# Driver.net
KiCad netlist of a schematic drawn in Altium Designer
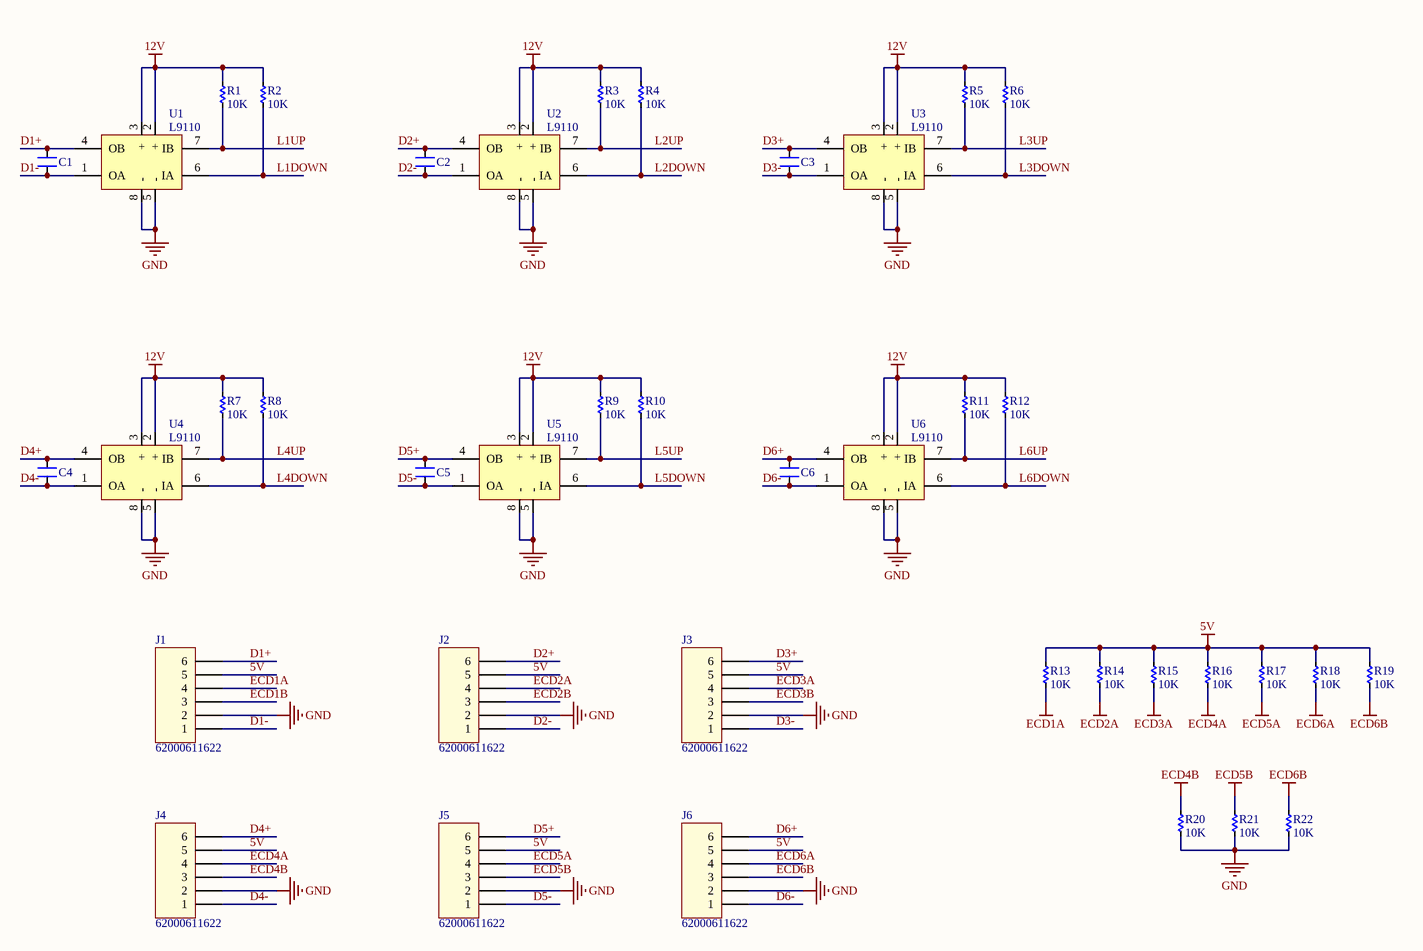
[diagram p0: Driver.SchDoc]

(export (version "E")
  (design (tool "Eeschema 10.0.6"))
  (components
    (comp (ref "C1") (value "XXpF") (footprint "CN2-LT") (libsource (lib "LIBRARY") (part "CN")))
    (comp (ref "C2") (value "XXpF") (footprint "CN2-LT") (libsource (lib "LIBRARY") (part "CN")))
    (comp (ref "C3") (value "XXpF") (footprint "CN2-LT") (libsource (lib "LIBRARY") (part "CN")))
    (comp (ref "C4") (value "XXpF") (footprint "CN2-LT") (libsource (lib "LIBRARY") (part "CN")))
    (comp (ref "C5") (value "XXpF") (footprint "CN2-LT") (libsource (lib "LIBRARY") (part "CN")))
    (comp (ref "C6") (value "XXpF") (footprint "CN2-LT") (libsource (lib "LIBRARY") (part "CN")))
    (comp (ref "J1")
      (value "62000611622")
      (footprint "62000611622")
      (description "WR-WTB 2.00mm Male Vertical Shrouded Header, 6p")
      (fields (field (name "PUBLISHER") "Wurth Elektronik"))
      (libsource (lib "Header2.0") (part "62000611622"))
    )
    (comp (ref "J2")
      (value "62000611622")
      (footprint "62000611622")
      (description "WR-WTB 2.00mm Male Vertical Shrouded Header, 6p")
      (fields (field (name "PUBLISHER") "Wurth Elektronik"))
      (libsource (lib "Header2.0") (part "62000611622"))
    )
    (comp (ref "J3")
      (value "62000611622")
      (footprint "62000611622")
      (description "WR-WTB 2.00mm Male Vertical Shrouded Header, 6p")
      (fields (field (name "PUBLISHER") "Wurth Elektronik"))
      (libsource (lib "Header2.0") (part "62000611622"))
    )
    (comp (ref "J4")
      (value "62000611622")
      (footprint "62000611622")
      (description "WR-WTB 2.00mm Male Vertical Shrouded Header, 6p")
      (fields (field (name "PUBLISHER") "Wurth Elektronik"))
      (libsource (lib "Header2.0") (part "62000611622"))
    )
    (comp (ref "J5")
      (value "62000611622")
      (footprint "62000611622")
      (description "WR-WTB 2.00mm Male Vertical Shrouded Header, 6p")
      (fields (field (name "PUBLISHER") "Wurth Elektronik"))
      (libsource (lib "Header2.0") (part "62000611622"))
    )
    (comp (ref "J6")
      (value "62000611622")
      (footprint "62000611622")
      (description "WR-WTB 2.00mm Male Vertical Shrouded Header, 6p")
      (fields (field (name "PUBLISHER") "Wurth Elektronik"))
      (libsource (lib "Header2.0") (part "62000611622"))
    )
    (comp (ref "R1")
      (value "10K")
      (footprint "RES-SMD-0805")
      (description "Resistor")
      (fields
        (field (name "MANUFACTURER") "Generic Components")
        (field (name "PUBLISHER") "Altium Hobart Technology Centre")
      )
      (libsource (lib "LIBRARY") (part "Res-SMD"))
    )
    (comp (ref "R2")
      (value "10K")
      (footprint "RES-SMD-0805")
      (description "Resistor")
      (fields
        (field (name "MANUFACTURER") "Generic Components")
        (field (name "PUBLISHER") "Altium Hobart Technology Centre")
      )
      (libsource (lib "LIBRARY") (part "Res-SMD"))
    )
    (comp (ref "R3")
      (value "10K")
      (footprint "RES-SMD-0805")
      (description "Resistor")
      (fields
        (field (name "MANUFACTURER") "Generic Components")
        (field (name "PUBLISHER") "Altium Hobart Technology Centre")
      )
      (libsource (lib "LIBRARY") (part "Res-SMD"))
    )
    (comp (ref "R4")
      (value "10K")
      (footprint "RES-SMD-0805")
      (description "Resistor")
      (fields
        (field (name "MANUFACTURER") "Generic Components")
        (field (name "PUBLISHER") "Altium Hobart Technology Centre")
      )
      (libsource (lib "LIBRARY") (part "Res-SMD"))
    )
    (comp (ref "R5")
      (value "10K")
      (footprint "RES-SMD-0805")
      (description "Resistor")
      (fields
        (field (name "MANUFACTURER") "Generic Components")
        (field (name "PUBLISHER") "Altium Hobart Technology Centre")
      )
      (libsource (lib "LIBRARY") (part "Res-SMD"))
    )
    (comp (ref "R6")
      (value "10K")
      (footprint "RES-SMD-0805")
      (description "Resistor")
      (fields
        (field (name "MANUFACTURER") "Generic Components")
        (field (name "PUBLISHER") "Altium Hobart Technology Centre")
      )
      (libsource (lib "LIBRARY") (part "Res-SMD"))
    )
    (comp (ref "R7")
      (value "10K")
      (footprint "RES-SMD-0805")
      (description "Resistor")
      (fields
        (field (name "MANUFACTURER") "Generic Components")
        (field (name "PUBLISHER") "Altium Hobart Technology Centre")
      )
      (libsource (lib "LIBRARY") (part "Res-SMD"))
    )
    (comp (ref "R8")
      (value "10K")
      (footprint "RES-SMD-0805")
      (description "Resistor")
      (fields
        (field (name "MANUFACTURER") "Generic Components")
        (field (name "PUBLISHER") "Altium Hobart Technology Centre")
      )
      (libsource (lib "LIBRARY") (part "Res-SMD"))
    )
    (comp (ref "R9")
      (value "10K")
      (footprint "RES-SMD-0805")
      (description "Resistor")
      (fields
        (field (name "MANUFACTURER") "Generic Components")
        (field (name "PUBLISHER") "Altium Hobart Technology Centre")
      )
      (libsource (lib "LIBRARY") (part "Res-SMD"))
    )
    (comp (ref "R10")
      (value "10K")
      (footprint "RES-SMD-0805")
      (description "Resistor")
      (fields
        (field (name "MANUFACTURER") "Generic Components")
        (field (name "PUBLISHER") "Altium Hobart Technology Centre")
      )
      (libsource (lib "LIBRARY") (part "Res-SMD"))
    )
    (comp (ref "R11")
      (value "10K")
      (footprint "RES-SMD-0805")
      (description "Resistor")
      (fields
        (field (name "MANUFACTURER") "Generic Components")
        (field (name "PUBLISHER") "Altium Hobart Technology Centre")
      )
      (libsource (lib "LIBRARY") (part "Res-SMD"))
    )
    (comp (ref "R12")
      (value "10K")
      (footprint "RES-SMD-0805")
      (description "Resistor")
      (fields
        (field (name "MANUFACTURER") "Generic Components")
        (field (name "PUBLISHER") "Altium Hobart Technology Centre")
      )
      (libsource (lib "LIBRARY") (part "Res-SMD"))
    )
    (comp (ref "R13")
      (value "10K")
      (footprint "RES-SMD-0805")
      (description "Resistor")
      (fields
        (field (name "MANUFACTURER") "Generic Components")
        (field (name "PUBLISHER") "Altium Hobart Technology Centre")
      )
      (libsource (lib "LIBRARY") (part "Res-SMD"))
    )
    (comp (ref "R14")
      (value "10K")
      (footprint "RES-SMD-0805")
      (description "Resistor")
      (fields
        (field (name "MANUFACTURER") "Generic Components")
        (field (name "PUBLISHER") "Altium Hobart Technology Centre")
      )
      (libsource (lib "LIBRARY") (part "Res-SMD"))
    )
    (comp (ref "R15")
      (value "10K")
      (footprint "RES-SMD-0805")
      (description "Resistor")
      (fields
        (field (name "MANUFACTURER") "Generic Components")
        (field (name "PUBLISHER") "Altium Hobart Technology Centre")
      )
      (libsource (lib "LIBRARY") (part "Res-SMD"))
    )
    (comp (ref "R16")
      (value "10K")
      (footprint "RES-SMD-0805")
      (description "Resistor")
      (fields
        (field (name "MANUFACTURER") "Generic Components")
        (field (name "PUBLISHER") "Altium Hobart Technology Centre")
      )
      (libsource (lib "LIBRARY") (part "Res-SMD"))
    )
    (comp (ref "R17")
      (value "10K")
      (footprint "RES-SMD-0805")
      (description "Resistor")
      (fields
        (field (name "MANUFACTURER") "Generic Components")
        (field (name "PUBLISHER") "Altium Hobart Technology Centre")
      )
      (libsource (lib "LIBRARY") (part "Res-SMD"))
    )
    (comp (ref "R18")
      (value "10K")
      (footprint "RES-SMD-0805")
      (description "Resistor")
      (fields
        (field (name "MANUFACTURER") "Generic Components")
        (field (name "PUBLISHER") "Altium Hobart Technology Centre")
      )
      (libsource (lib "LIBRARY") (part "Res-SMD"))
    )
    (comp (ref "R19")
      (value "10K")
      (footprint "RES-SMD-0805")
      (description "Resistor")
      (fields
        (field (name "MANUFACTURER") "Generic Components")
        (field (name "PUBLISHER") "Altium Hobart Technology Centre")
      )
      (libsource (lib "LIBRARY") (part "Res-SMD"))
    )
    (comp (ref "R20")
      (value "10K")
      (footprint "RES-SMD-0805")
      (description "Resistor")
      (fields
        (field (name "MANUFACTURER") "Generic Components")
        (field (name "PUBLISHER") "Altium Hobart Technology Centre")
      )
      (libsource (lib "LIBRARY") (part "Res-SMD"))
    )
    (comp (ref "R21")
      (value "10K")
      (footprint "RES-SMD-0805")
      (description "Resistor")
      (fields
        (field (name "MANUFACTURER") "Generic Components")
        (field (name "PUBLISHER") "Altium Hobart Technology Centre")
      )
      (libsource (lib "LIBRARY") (part "Res-SMD"))
    )
    (comp (ref "R22")
      (value "10K")
      (footprint "RES-SMD-0805")
      (description "Resistor")
      (fields
        (field (name "MANUFACTURER") "Generic Components")
        (field (name "PUBLISHER") "Altium Hobart Technology Centre")
      )
      (libsource (lib "LIBRARY") (part "Res-SMD"))
    )
    (comp (ref "U1")
      (value "L9110")
      (footprint "DIP8")
      (description "Half-Bridge Driver")
      (libsource (lib "LIBRARY") (part "L9110"))
    )
    (comp (ref "U2")
      (value "L9110")
      (footprint "DIP8")
      (description "Half-Bridge Driver")
      (libsource (lib "LIBRARY") (part "L9110"))
    )
    (comp (ref "U3")
      (value "L9110")
      (footprint "DIP8")
      (description "Half-Bridge Driver")
      (libsource (lib "LIBRARY") (part "L9110"))
    )
    (comp (ref "U4")
      (value "L9110")
      (footprint "DIP8")
      (description "Half-Bridge Driver")
      (libsource (lib "LIBRARY") (part "L9110"))
    )
    (comp (ref "U5")
      (value "L9110")
      (footprint "DIP8")
      (description "Half-Bridge Driver")
      (libsource (lib "LIBRARY") (part "L9110"))
    )
    (comp (ref "U6")
      (value "L9110")
      (footprint "DIP8")
      (description "Half-Bridge Driver")
      (libsource (lib "LIBRARY") (part "L9110"))
    )
  )
  (nets
    (net (code "1") (name "/D1+") (class "Default")
      (node (ref "C1") (pin "2") (pinfunction "2_2") (pintype "passive"))
      (node (ref "J1") (pin "6") (pinfunction "6_6") (pintype "passive"))
      (node (ref "U1") (pin "4") (pinfunction "OB_4") (pintype "passive"))
    )
    (net (code "2") (name "/D1-") (class "Default")
      (node (ref "C1") (pin "1") (pinfunction "1_1") (pintype "passive"))
      (node (ref "J1") (pin "1") (pinfunction "1_1") (pintype "passive"))
      (node (ref "U1") (pin "1") (pinfunction "OA_1") (pintype "passive"))
    )
    (net (code "3") (name "/D2+") (class "Default")
      (node (ref "C2") (pin "2") (pinfunction "2_2") (pintype "passive"))
      (node (ref "J2") (pin "6") (pinfunction "6_6") (pintype "passive"))
      (node (ref "U2") (pin "4") (pinfunction "OB_4") (pintype "passive"))
    )
    (net (code "4") (name "/D2-") (class "Default")
      (node (ref "C2") (pin "1") (pinfunction "1_1") (pintype "passive"))
      (node (ref "J2") (pin "1") (pinfunction "1_1") (pintype "passive"))
      (node (ref "U2") (pin "1") (pinfunction "OA_1") (pintype "passive"))
    )
    (net (code "5") (name "/D3+") (class "Default")
      (node (ref "C3") (pin "2") (pinfunction "2_2") (pintype "passive"))
      (node (ref "J3") (pin "6") (pinfunction "6_6") (pintype "passive"))
      (node (ref "U3") (pin "4") (pinfunction "OB_4") (pintype "passive"))
    )
    (net (code "6") (name "/D3-") (class "Default")
      (node (ref "C3") (pin "1") (pinfunction "1_1") (pintype "passive"))
      (node (ref "J3") (pin "1") (pinfunction "1_1") (pintype "passive"))
      (node (ref "U3") (pin "1") (pinfunction "OA_1") (pintype "passive"))
    )
    (net (code "7") (name "/D4+") (class "Default")
      (node (ref "C4") (pin "2") (pinfunction "2_2") (pintype "passive"))
      (node (ref "J4") (pin "6") (pinfunction "6_6") (pintype "passive"))
      (node (ref "U4") (pin "4") (pinfunction "OB_4") (pintype "passive"))
    )
    (net (code "8") (name "/D4-") (class "Default")
      (node (ref "C4") (pin "1") (pinfunction "1_1") (pintype "passive"))
      (node (ref "J4") (pin "1") (pinfunction "1_1") (pintype "passive"))
      (node (ref "U4") (pin "1") (pinfunction "OA_1") (pintype "passive"))
    )
    (net (code "9") (name "/D5+") (class "Default")
      (node (ref "C5") (pin "2") (pinfunction "2_2") (pintype "passive"))
      (node (ref "J5") (pin "6") (pinfunction "6_6") (pintype "passive"))
      (node (ref "U5") (pin "4") (pinfunction "OB_4") (pintype "passive"))
    )
    (net (code "10") (name "/D5-") (class "Default")
      (node (ref "C5") (pin "1") (pinfunction "1_1") (pintype "passive"))
      (node (ref "J5") (pin "1") (pinfunction "1_1") (pintype "passive"))
      (node (ref "U5") (pin "1") (pinfunction "OA_1") (pintype "passive"))
    )
    (net (code "11") (name "/D6+") (class "Default")
      (node (ref "C6") (pin "2") (pinfunction "2_2") (pintype "passive"))
      (node (ref "J6") (pin "6") (pinfunction "6_6") (pintype "passive"))
      (node (ref "U6") (pin "4") (pinfunction "OB_4") (pintype "passive"))
    )
    (net (code "12") (name "/D6-") (class "Default")
      (node (ref "C6") (pin "1") (pinfunction "1_1") (pintype "passive"))
      (node (ref "J6") (pin "1") (pinfunction "1_1") (pintype "passive"))
      (node (ref "U6") (pin "1") (pinfunction "OA_1") (pintype "passive"))
    )
    (net (code "13") (name "/ECD1B") (class "Default")
      (node (ref "J1") (pin "3") (pinfunction "3_3") (pintype "passive"))
    )
    (net (code "14") (name "/ECD2B") (class "Default")
      (node (ref "J2") (pin "3") (pinfunction "3_3") (pintype "passive"))
    )
    (net (code "15") (name "/ECD3B") (class "Default")
      (node (ref "J3") (pin "3") (pinfunction "3_3") (pintype "passive"))
    )
    (net (code "16") (name "/L1DOWN") (class "Default")
      (node (ref "R2") (pin "2") (pinfunction "2_2") (pintype "passive"))
      (node (ref "U1") (pin "6") (pinfunction "IA_6") (pintype "passive"))
    )
    (net (code "17") (name "/L1UP") (class "Default")
      (node (ref "R1") (pin "2") (pinfunction "2_2") (pintype "passive"))
      (node (ref "U1") (pin "7") (pinfunction "IB_7") (pintype "passive"))
    )
    (net (code "18") (name "/L2DOWN") (class "Default")
      (node (ref "R4") (pin "2") (pinfunction "2_2") (pintype "passive"))
      (node (ref "U2") (pin "6") (pinfunction "IA_6") (pintype "passive"))
    )
    (net (code "19") (name "/L2UP") (class "Default")
      (node (ref "R3") (pin "2") (pinfunction "2_2") (pintype "passive"))
      (node (ref "U2") (pin "7") (pinfunction "IB_7") (pintype "passive"))
    )
    (net (code "20") (name "/L3DOWN") (class "Default")
      (node (ref "R6") (pin "2") (pinfunction "2_2") (pintype "passive"))
      (node (ref "U3") (pin "6") (pinfunction "IA_6") (pintype "passive"))
    )
    (net (code "21") (name "/L3UP") (class "Default")
      (node (ref "R5") (pin "2") (pinfunction "2_2") (pintype "passive"))
      (node (ref "U3") (pin "7") (pinfunction "IB_7") (pintype "passive"))
    )
    (net (code "22") (name "/L4DOWN") (class "Default")
      (node (ref "R8") (pin "2") (pinfunction "2_2") (pintype "passive"))
      (node (ref "U4") (pin "6") (pinfunction "IA_6") (pintype "passive"))
    )
    (net (code "23") (name "/L4UP") (class "Default")
      (node (ref "R7") (pin "2") (pinfunction "2_2") (pintype "passive"))
      (node (ref "U4") (pin "7") (pinfunction "IB_7") (pintype "passive"))
    )
    (net (code "24") (name "/L5DOWN") (class "Default")
      (node (ref "R10") (pin "2") (pinfunction "2_2") (pintype "passive"))
      (node (ref "U5") (pin "6") (pinfunction "IA_6") (pintype "passive"))
    )
    (net (code "25") (name "/L5UP") (class "Default")
      (node (ref "R9") (pin "2") (pinfunction "2_2") (pintype "passive"))
      (node (ref "U5") (pin "7") (pinfunction "IB_7") (pintype "passive"))
    )
    (net (code "26") (name "/L6DOWN") (class "Default")
      (node (ref "R12") (pin "2") (pinfunction "2_2") (pintype "passive"))
      (node (ref "U6") (pin "6") (pinfunction "IA_6") (pintype "passive"))
    )
    (net (code "27") (name "/L6UP") (class "Default")
      (node (ref "R11") (pin "2") (pinfunction "2_2") (pintype "passive"))
      (node (ref "U6") (pin "7") (pinfunction "IB_7") (pintype "passive"))
    )
    (net (code "28") (name "5V") (class "Default")
      (node (ref "J1") (pin "5") (pinfunction "5_5") (pintype "passive"))
      (node (ref "J2") (pin "5") (pinfunction "5_5") (pintype "passive"))
      (node (ref "J3") (pin "5") (pinfunction "5_5") (pintype "passive"))
      (node (ref "J4") (pin "5") (pinfunction "5_5") (pintype "passive"))
      (node (ref "J5") (pin "5") (pinfunction "5_5") (pintype "passive"))
      (node (ref "J6") (pin "5") (pinfunction "5_5") (pintype "passive"))
      (node (ref "R13") (pin "1") (pinfunction "1_1") (pintype "passive"))
      (node (ref "R14") (pin "1") (pinfunction "1_1") (pintype "passive"))
      (node (ref "R15") (pin "1") (pinfunction "1_1") (pintype "passive"))
      (node (ref "R16") (pin "1") (pinfunction "1_1") (pintype "passive"))
      (node (ref "R17") (pin "1") (pinfunction "1_1") (pintype "passive"))
      (node (ref "R18") (pin "1") (pinfunction "1_1") (pintype "passive"))
      (node (ref "R19") (pin "1") (pinfunction "1_1") (pintype "passive"))
    )
    (net (code "29") (name "12V") (class "Default")
      (node (ref "R1") (pin "1") (pinfunction "1_1") (pintype "passive"))
      (node (ref "R10") (pin "1") (pinfunction "1_1") (pintype "passive"))
      (node (ref "R11") (pin "1") (pinfunction "1_1") (pintype "passive"))
      (node (ref "R12") (pin "1") (pinfunction "1_1") (pintype "passive"))
      (node (ref "R2") (pin "1") (pinfunction "1_1") (pintype "passive"))
      (node (ref "R3") (pin "1") (pinfunction "1_1") (pintype "passive"))
      (node (ref "R4") (pin "1") (pinfunction "1_1") (pintype "passive"))
      (node (ref "R5") (pin "1") (pinfunction "1_1") (pintype "passive"))
      (node (ref "R6") (pin "1") (pinfunction "1_1") (pintype "passive"))
      (node (ref "R7") (pin "1") (pinfunction "1_1") (pintype "passive"))
      (node (ref "R8") (pin "1") (pinfunction "1_1") (pintype "passive"))
      (node (ref "R9") (pin "1") (pinfunction "1_1") (pintype "passive"))
      (node (ref "U1") (pin "2") (pinfunction "+_2") (pintype "passive"))
      (node (ref "U1") (pin "3") (pinfunction "+_3") (pintype "passive"))
      (node (ref "U2") (pin "2") (pinfunction "+_2") (pintype "passive"))
      (node (ref "U2") (pin "3") (pinfunction "+_3") (pintype "passive"))
      (node (ref "U3") (pin "2") (pinfunction "+_2") (pintype "passive"))
      (node (ref "U3") (pin "3") (pinfunction "+_3") (pintype "passive"))
      (node (ref "U4") (pin "2") (pinfunction "+_2") (pintype "passive"))
      (node (ref "U4") (pin "3") (pinfunction "+_3") (pintype "passive"))
      (node (ref "U5") (pin "2") (pinfunction "+_2") (pintype "passive"))
      (node (ref "U5") (pin "3") (pinfunction "+_3") (pintype "passive"))
      (node (ref "U6") (pin "2") (pinfunction "+_2") (pintype "passive"))
      (node (ref "U6") (pin "3") (pinfunction "+_3") (pintype "passive"))
    )
    (net (code "30") (name "ECD1A") (class "Default")
      (node (ref "J1") (pin "4") (pinfunction "4_4") (pintype "passive"))
      (node (ref "R13") (pin "2") (pinfunction "2_2") (pintype "passive"))
    )
    (net (code "31") (name "ECD2A") (class "Default")
      (node (ref "J2") (pin "4") (pinfunction "4_4") (pintype "passive"))
      (node (ref "R14") (pin "2") (pinfunction "2_2") (pintype "passive"))
    )
    (net (code "32") (name "ECD3A") (class "Default")
      (node (ref "J3") (pin "4") (pinfunction "4_4") (pintype "passive"))
      (node (ref "R15") (pin "2") (pinfunction "2_2") (pintype "passive"))
    )
    (net (code "33") (name "ECD4A") (class "Default")
      (node (ref "J4") (pin "4") (pinfunction "4_4") (pintype "passive"))
      (node (ref "R16") (pin "2") (pinfunction "2_2") (pintype "passive"))
    )
    (net (code "34") (name "ECD4B") (class "Default")
      (node (ref "J4") (pin "3") (pinfunction "3_3") (pintype "passive"))
      (node (ref "R20") (pin "2") (pinfunction "2_2") (pintype "passive"))
    )
    (net (code "35") (name "ECD5A") (class "Default")
      (node (ref "J5") (pin "4") (pinfunction "4_4") (pintype "passive"))
      (node (ref "R17") (pin "2") (pinfunction "2_2") (pintype "passive"))
    )
    (net (code "36") (name "ECD5B") (class "Default")
      (node (ref "J5") (pin "3") (pinfunction "3_3") (pintype "passive"))
      (node (ref "R21") (pin "2") (pinfunction "2_2") (pintype "passive"))
    )
    (net (code "37") (name "ECD6A") (class "Default")
      (node (ref "J6") (pin "4") (pinfunction "4_4") (pintype "passive"))
      (node (ref "R18") (pin "2") (pinfunction "2_2") (pintype "passive"))
    )
    (net (code "38") (name "ECD6B") (class "Default")
      (node (ref "J6") (pin "3") (pinfunction "3_3") (pintype "passive"))
      (node (ref "R19") (pin "2") (pinfunction "2_2") (pintype "passive"))
      (node (ref "R22") (pin "2") (pinfunction "2_2") (pintype "passive"))
    )
    (net (code "39") (name "GND") (class "Default")
      (node (ref "J1") (pin "2") (pinfunction "2_2") (pintype "passive"))
      (node (ref "J2") (pin "2") (pinfunction "2_2") (pintype "passive"))
      (node (ref "J3") (pin "2") (pinfunction "2_2") (pintype "passive"))
      (node (ref "J4") (pin "2") (pinfunction "2_2") (pintype "passive"))
      (node (ref "J5") (pin "2") (pinfunction "2_2") (pintype "passive"))
      (node (ref "J6") (pin "2") (pinfunction "2_2") (pintype "passive"))
      (node (ref "R20") (pin "1") (pinfunction "1_1") (pintype "passive"))
      (node (ref "R21") (pin "1") (pinfunction "1_1") (pintype "passive"))
      (node (ref "R22") (pin "1") (pinfunction "1_1") (pintype "passive"))
      (node (ref "U1") (pin "5") (pinfunction "-_5") (pintype "passive"))
      (node (ref "U1") (pin "8") (pinfunction "-_8") (pintype "passive"))
      (node (ref "U2") (pin "5") (pinfunction "-_5") (pintype "passive"))
      (node (ref "U2") (pin "8") (pinfunction "-_8") (pintype "passive"))
      (node (ref "U3") (pin "5") (pinfunction "-_5") (pintype "passive"))
      (node (ref "U3") (pin "8") (pinfunction "-_8") (pintype "passive"))
      (node (ref "U4") (pin "5") (pinfunction "-_5") (pintype "passive"))
      (node (ref "U4") (pin "8") (pinfunction "-_8") (pintype "passive"))
      (node (ref "U5") (pin "5") (pinfunction "-_5") (pintype "passive"))
      (node (ref "U5") (pin "8") (pinfunction "-_8") (pintype "passive"))
      (node (ref "U6") (pin "5") (pinfunction "-_5") (pintype "passive"))
      (node (ref "U6") (pin "8") (pinfunction "-_8") (pintype "passive"))
    )
  )
)
